# LPCB279_-_ANALOG_INPUTS.net
KiCad netlist of a schematic drawn in Altium Designer
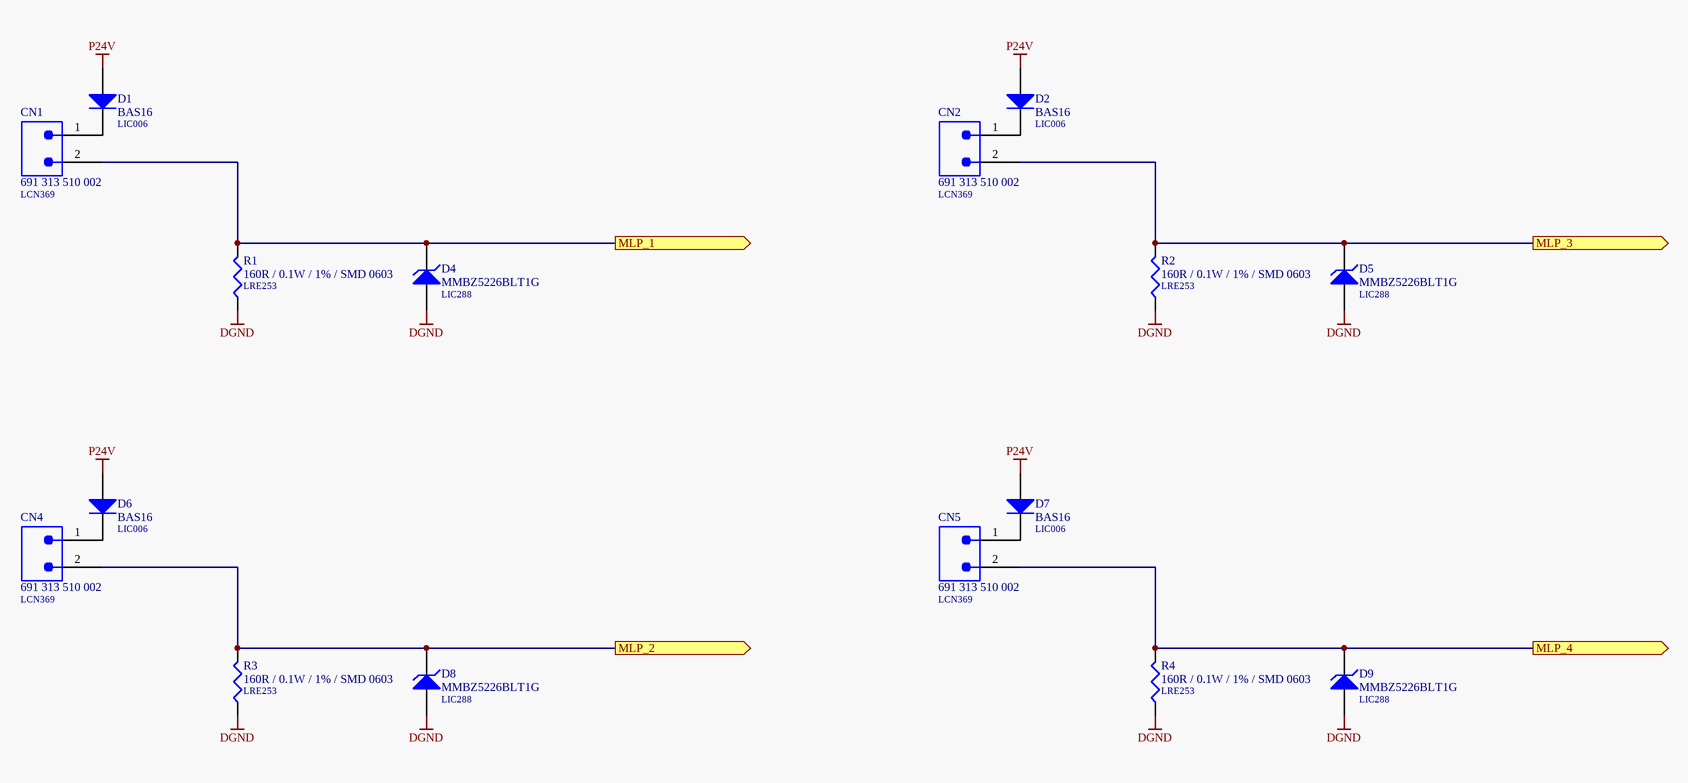
[diagram p0: LPCB279 - ANALOG INPUTS.SchDoc]

(export (version "E")
  (design (tool "Eeschema 10.0.6"))
  (components
    (comp (ref "CN1")
      (value "691 313 510 002")
      (footprint "691 313 510 002")
      (description "Connector, Pluggable Terminal Block, 5.08mm, 2 Way, PTH")
      (fields (field (name "LDL_NUMBER") "LCN369"))
      (libsource (lib "LDL_Connectors") (part "691 313 510 002"))
    )
    (comp (ref "CN2")
      (value "691 313 510 002")
      (footprint "691 313 510 002")
      (description "Connector, Pluggable Terminal Block, 5.08mm, 2 Way, PTH")
      (fields (field (name "LDL_NUMBER") "LCN369"))
      (libsource (lib "LDL_Connectors") (part "691 313 510 002"))
    )
    (comp (ref "CN4")
      (value "691 313 510 002")
      (footprint "691 313 510 002")
      (description "Connector, Pluggable Terminal Block, 5.08mm, 2 Way, PTH")
      (fields (field (name "LDL_NUMBER") "LCN369"))
      (libsource (lib "LDL_Connectors") (part "691 313 510 002"))
    )
    (comp (ref "CN5")
      (value "691 313 510 002")
      (footprint "691 313 510 002")
      (description "Connector, Pluggable Terminal Block, 5.08mm, 2 Way, PTH")
      (fields (field (name "LDL_NUMBER") "LCN369"))
      (libsource (lib "LDL_Connectors") (part "691 313 510 002"))
    )
    (comp (ref "D1")
      (value "BAS16")
      (footprint "LFP021__SOT23")
      (description "Diode, Small Signal, 0.2A, 85V, SMD SOT-23 [LIC006]")
      (fields (field (name "LDL_NUMBER") "LIC006"))
      (libsource (lib "LDL_Semiconductors") (part "BAS16"))
    )
    (comp (ref "D2")
      (value "BAS16")
      (footprint "LFP021__SOT23")
      (description "Diode, Small Signal, 0.2A, 85V, SMD SOT-23 [LIC006]")
      (fields (field (name "LDL_NUMBER") "LIC006"))
      (libsource (lib "LDL_Semiconductors") (part "BAS16"))
    )
    (comp (ref "D4")
      (value "MMBZ5226BLT1G")
      (footprint "LFP021__SOT23")
      (description "Diode, Zener, 3.3V, 0.225W, SMD [LIC288]")
      (fields (field (name "LDL_NUMBER") "LIC288"))
      (libsource (lib "LDL_Semiconductors") (part "MMBZ5226BLT1G"))
    )
    (comp (ref "D5")
      (value "MMBZ5226BLT1G")
      (footprint "LFP021__SOT23")
      (description "Diode, Zener, 3.3V, 0.225W, SMD [LIC288]")
      (fields (field (name "LDL_NUMBER") "LIC288"))
      (libsource (lib "LDL_Semiconductors") (part "MMBZ5226BLT1G"))
    )
    (comp (ref "D6")
      (value "BAS16")
      (footprint "LFP021__SOT23")
      (description "Diode, Small Signal, 0.2A, 85V, SMD SOT-23 [LIC006]")
      (fields (field (name "LDL_NUMBER") "LIC006"))
      (libsource (lib "LDL_Semiconductors") (part "BAS16"))
    )
    (comp (ref "D7")
      (value "BAS16")
      (footprint "LFP021__SOT23")
      (description "Diode, Small Signal, 0.2A, 85V, SMD SOT-23 [LIC006]")
      (fields (field (name "LDL_NUMBER") "LIC006"))
      (libsource (lib "LDL_Semiconductors") (part "BAS16"))
    )
    (comp (ref "D8")
      (value "MMBZ5226BLT1G")
      (footprint "LFP021__SOT23")
      (description "Diode, Zener, 3.3V, 0.225W, SMD [LIC288]")
      (fields (field (name "LDL_NUMBER") "LIC288"))
      (libsource (lib "LDL_Semiconductors") (part "MMBZ5226BLT1G"))
    )
    (comp (ref "D9")
      (value "MMBZ5226BLT1G")
      (footprint "LFP021__SOT23")
      (description "Diode, Zener, 3.3V, 0.225W, SMD [LIC288]")
      (fields (field (name "LDL_NUMBER") "LIC288"))
      (libsource (lib "LDL_Semiconductors") (part "MMBZ5226BLT1G"))
    )
    (comp (ref "R1")
      (value "160R / 0.1W / 1% / SMD 0603")
      (footprint "LFP020__CR1608-0603-IPC7351_B")
      (description "Resistor, Ceramic Chip, 160R, 0.1W, 1%, SMD 0603 [LRE253]")
      (fields (field (name "LDL_NUMBER") "LRE253"))
      (libsource (lib "LDL_Resistors") (part "160R / 0.1W / 1% / SMD 0603"))
    )
    (comp (ref "R2")
      (value "160R / 0.1W / 1% / SMD 0603")
      (footprint "LFP020__CR1608-0603-IPC7351_B")
      (description "Resistor, Ceramic Chip, 160R, 0.1W, 1%, SMD 0603 [LRE253]")
      (fields (field (name "LDL_NUMBER") "LRE253"))
      (libsource (lib "LDL_Resistors") (part "160R / 0.1W / 1% / SMD 0603"))
    )
    (comp (ref "R3")
      (value "160R / 0.1W / 1% / SMD 0603")
      (footprint "LFP020__CR1608-0603-IPC7351_B")
      (description "Resistor, Ceramic Chip, 160R, 0.1W, 1%, SMD 0603 [LRE253]")
      (fields (field (name "LDL_NUMBER") "LRE253"))
      (libsource (lib "LDL_Resistors") (part "160R / 0.1W / 1% / SMD 0603"))
    )
    (comp (ref "R4")
      (value "160R / 0.1W / 1% / SMD 0603")
      (footprint "LFP020__CR1608-0603-IPC7351_B")
      (description "Resistor, Ceramic Chip, 160R, 0.1W, 1%, SMD 0603 [LRE253]")
      (fields (field (name "LDL_NUMBER") "LRE253"))
      (libsource (lib "LDL_Resistors") (part "160R / 0.1W / 1% / SMD 0603"))
    )
  )
  (nets
    (net (code "1") (name "/MLP_1") (class "Default")
      (node (ref "CN1") (pin "2") (pinfunction "2_2") (pintype "passive"))
      (node (ref "D4") (pin "3") (pinfunction "K_3") (pintype "passive"))
      (node (ref "R1") (pin "2") (pintype "passive"))
    )
    (net (code "2") (name "/MLP_2") (class "Default")
      (node (ref "CN4") (pin "2") (pinfunction "2_2") (pintype "passive"))
      (node (ref "D8") (pin "3") (pinfunction "K_3") (pintype "passive"))
      (node (ref "R3") (pin "2") (pintype "passive"))
    )
    (net (code "3") (name "/MLP_3") (class "Default")
      (node (ref "CN2") (pin "2") (pinfunction "2_2") (pintype "passive"))
      (node (ref "D5") (pin "3") (pinfunction "K_3") (pintype "passive"))
      (node (ref "R2") (pin "2") (pintype "passive"))
    )
    (net (code "4") (name "/MLP_4") (class "Default")
      (node (ref "CN5") (pin "2") (pinfunction "2_2") (pintype "passive"))
      (node (ref "D9") (pin "3") (pinfunction "K_3") (pintype "passive"))
      (node (ref "R4") (pin "2") (pintype "passive"))
    )
    (net (code "5") (name "DGND") (class "Default")
      (node (ref "D4") (pin "1") (pinfunction "A_1") (pintype "passive"))
      (node (ref "D5") (pin "1") (pinfunction "A_1") (pintype "passive"))
      (node (ref "D8") (pin "1") (pinfunction "A_1") (pintype "passive"))
      (node (ref "D9") (pin "1") (pinfunction "A_1") (pintype "passive"))
      (node (ref "R1") (pin "1") (pintype "passive"))
      (node (ref "R2") (pin "1") (pintype "passive"))
      (node (ref "R3") (pin "1") (pintype "passive"))
      (node (ref "R4") (pin "1") (pintype "passive"))
    )
    (net (code "6") (name "Net-(D1-K)") (class "Default")
      (node (ref "CN1") (pin "1") (pinfunction "1_1") (pintype "passive"))
      (node (ref "D1") (pin "3") (pinfunction "K_3") (pintype "passive"))
    )
    (net (code "7") (name "Net-(D2-K)") (class "Default")
      (node (ref "CN2") (pin "1") (pinfunction "1_1") (pintype "passive"))
      (node (ref "D2") (pin "3") (pinfunction "K_3") (pintype "passive"))
    )
    (net (code "8") (name "Net-(D6-K)") (class "Default")
      (node (ref "CN4") (pin "1") (pinfunction "1_1") (pintype "passive"))
      (node (ref "D6") (pin "3") (pinfunction "K_3") (pintype "passive"))
    )
    (net (code "9") (name "Net-(D7-K)") (class "Default")
      (node (ref "CN5") (pin "1") (pinfunction "1_1") (pintype "passive"))
      (node (ref "D7") (pin "3") (pinfunction "K_3") (pintype "passive"))
    )
    (net (code "10") (name "P24V") (class "Default")
      (node (ref "D1") (pin "1") (pinfunction "A_1") (pintype "passive"))
      (node (ref "D2") (pin "1") (pinfunction "A_1") (pintype "passive"))
      (node (ref "D6") (pin "1") (pinfunction "A_1") (pintype "passive"))
      (node (ref "D7") (pin "1") (pinfunction "A_1") (pintype "passive"))
    )
  )
)
